# PlusBit_MCU.net
KiCad netlist of a schematic drawn in Altium Designer
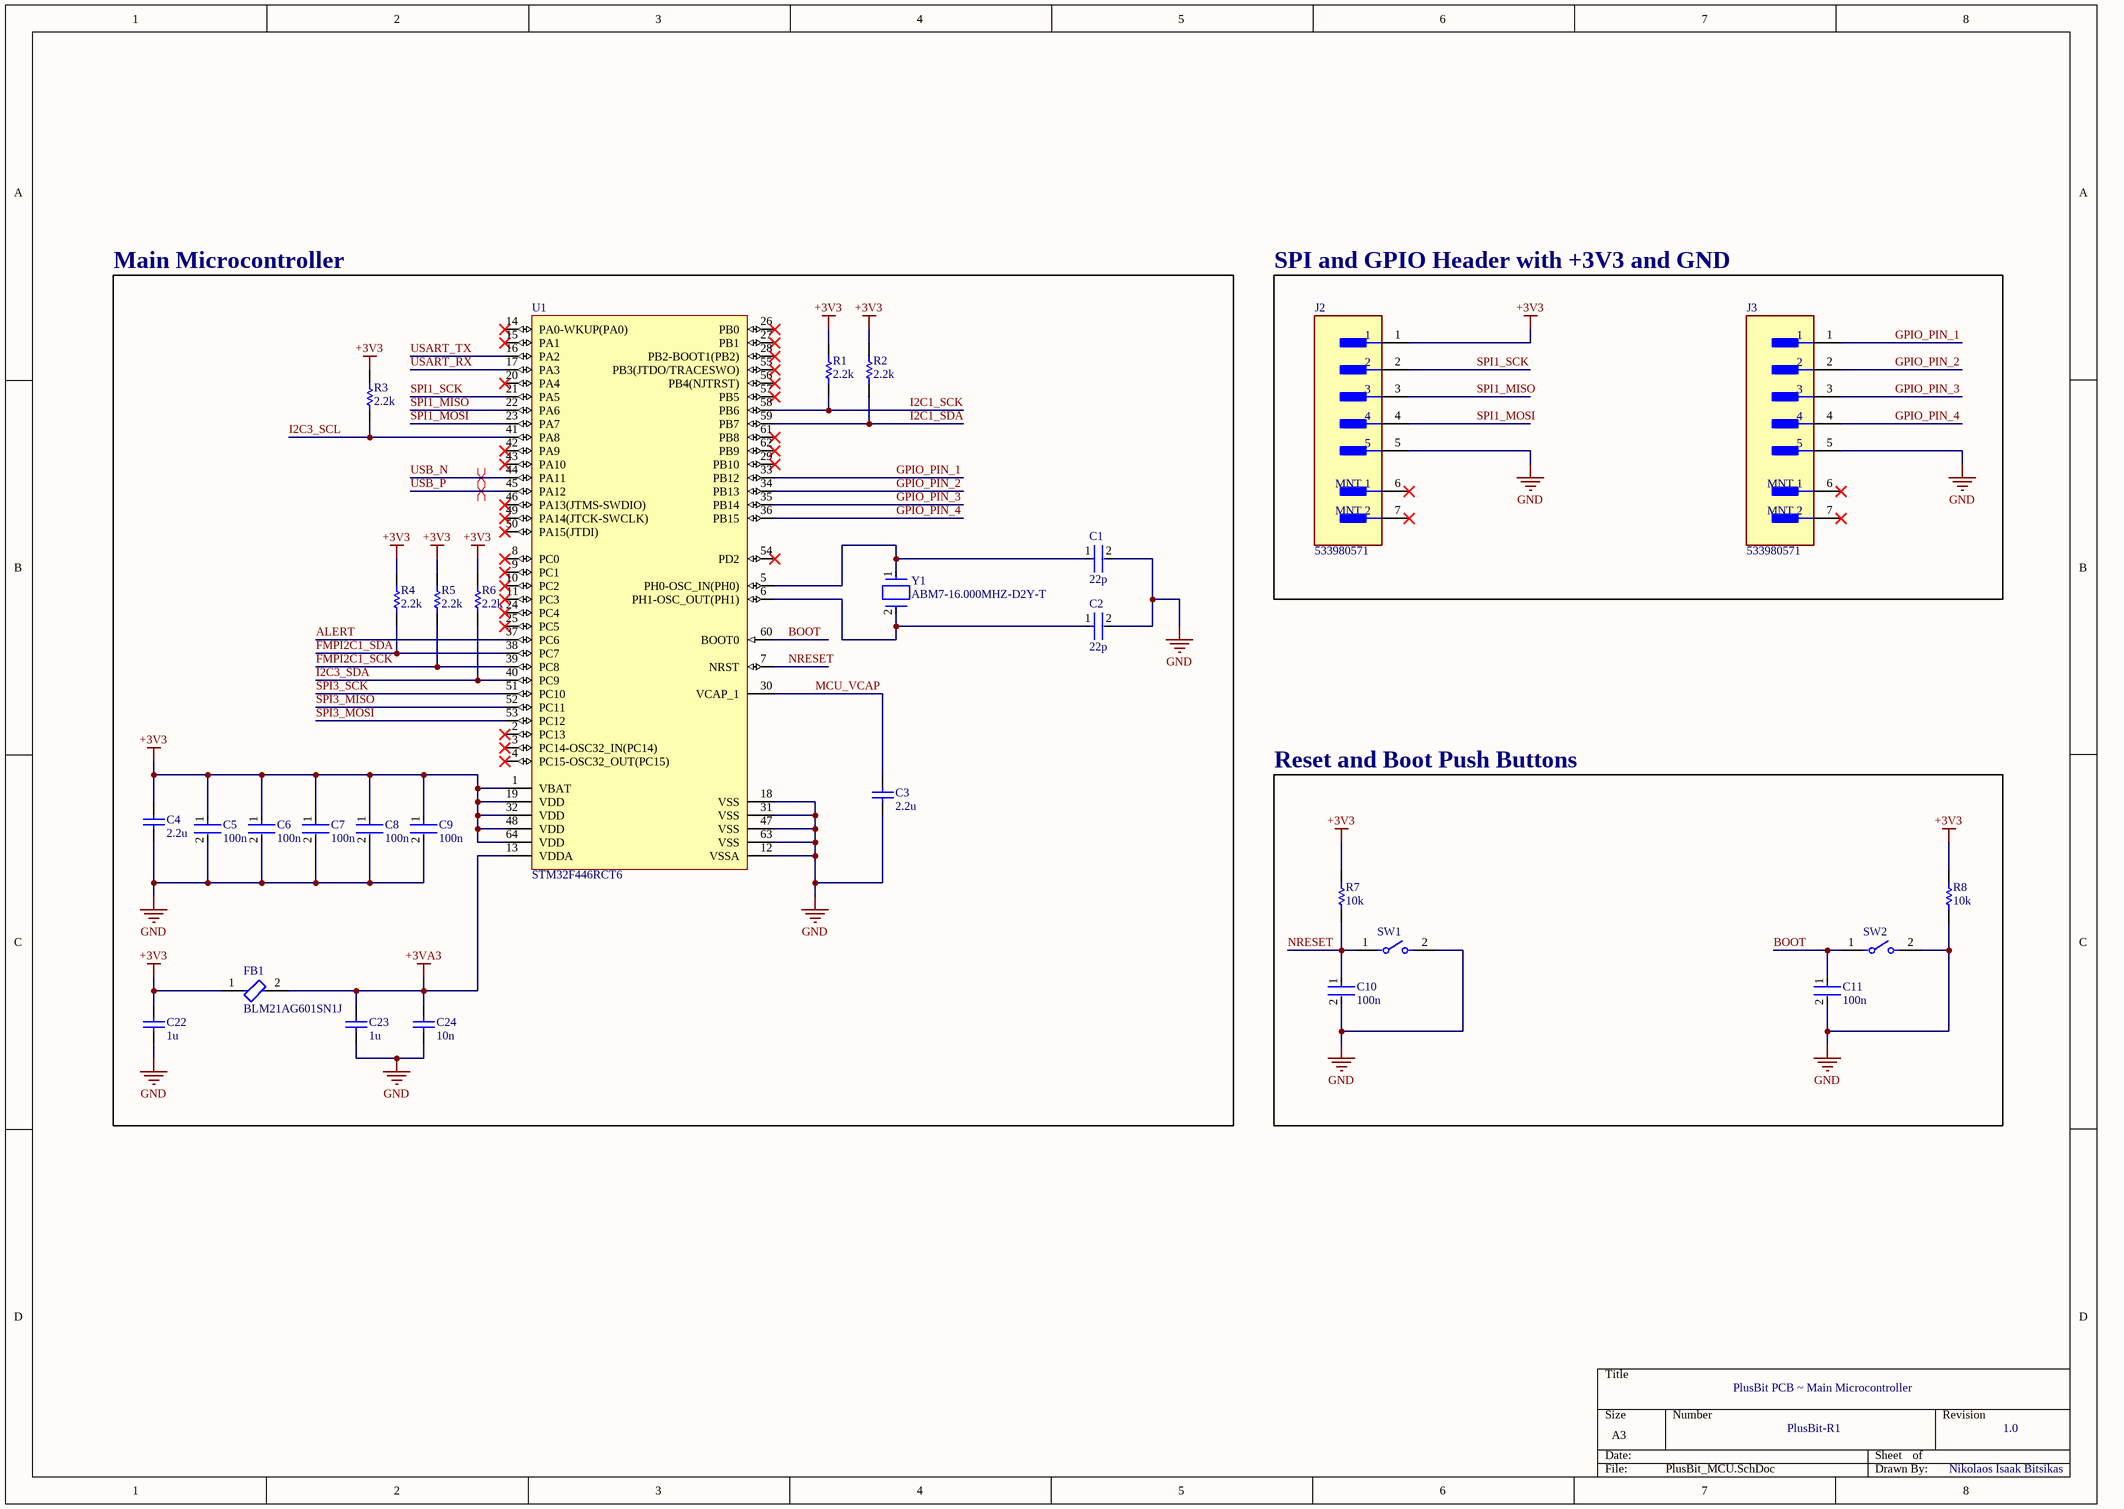
[diagram p0: PlusBit_MCU.SchDoc]

(export (version "E")
  (design (tool "Eeschema 10.0.6"))
  (components
    (comp (ref "C1")
      (value "22p")
      (footprint "FP-C1206C-EB-MFG")
      (description "1206 22pF Ceramic Multilayer Capacitor; 50VDC; 125degC; C0G Dielec; +/-5% SMD")
      (fields
        (field (name "OCTOPART") "https://octopart.com/c1206c220j5gactu-kemet-131912")
        (field (name "TOLERANCE") "0.05")
      )
      (libsource (lib "Altium Content Vault") (part "b4654b650e69147ec39a6b967a45e02"))
    )
    (comp (ref "C2")
      (value "22p")
      (footprint "FP-C1206C-EB-MFG")
      (description "1206 22pF Ceramic Multilayer Capacitor; 50VDC; 125degC; C0G Dielec; +/-5% SMD")
      (fields
        (field (name "OCTOPART") "https://octopart.com/c1206c220j5gactu-kemet-131912")
        (field (name "TOLERANCE") "0.05")
      )
      (libsource (lib "Altium Content Vault") (part "b4654b650e69147ec39a6b967a45e02"))
    )
    (comp (ref "C3")
      (value "2.2u")
      (footprint "CAPC2013X145X50ML20T25")
      (fields (field (name "PART NUMBER") "C0805C225K9PACTU") (field (name "MANUFACTURER") "Kemet"))
      (libsource (lib "Altium Content Vault") (part "CAP"))
    )
    (comp (ref "C4")
      (value "2.2u")
      (footprint "CAPC2013X145X50ML20T25")
      (fields (field (name "PART NUMBER") "C0805C225K9PACTU") (field (name "MANUFACTURER") "Kemet"))
      (libsource (lib "Altium Content Vault") (part "CAP"))
    )
    (comp (ref "C5")
      (value "100n")
      (footprint "FP-C0402-BB-MFG")
      (description "CAP CER 0.1UF 10V X5R 0402")
      (fields (field (name "MANUFACTURER") "Kemet") (field (name "TOLERANCE") "0.1"))
      (libsource (lib "Altium Content Vault") (part "b4654b650e69147ec39a6b967a45e02"))
    )
    (comp (ref "C6")
      (value "100n")
      (footprint "FP-C0402-BB-MFG")
      (description "CAP CER 0.1UF 10V X5R 0402")
      (fields (field (name "MANUFACTURER") "Kemet") (field (name "TOLERANCE") "0.1"))
      (libsource (lib "Altium Content Vault") (part "b4654b650e69147ec39a6b967a45e02"))
    )
    (comp (ref "C7")
      (value "100n")
      (footprint "FP-C0402-BB-MFG")
      (description "CAP CER 0.1UF 10V X5R 0402")
      (fields (field (name "MANUFACTURER") "Kemet") (field (name "TOLERANCE") "0.1"))
      (libsource (lib "Altium Content Vault") (part "b4654b650e69147ec39a6b967a45e02"))
    )
    (comp (ref "C8")
      (value "100n")
      (footprint "FP-C0402-BB-MFG")
      (description "CAP CER 0.1UF 10V X5R 0402")
      (fields (field (name "MANUFACTURER") "Kemet") (field (name "TOLERANCE") "0.1"))
      (libsource (lib "Altium Content Vault") (part "b4654b650e69147ec39a6b967a45e02"))
    )
    (comp (ref "C9")
      (value "100n")
      (footprint "FP-C0402-BB-MFG")
      (description "CAP CER 0.1UF 10V X5R 0402")
      (fields (field (name "MANUFACTURER") "Kemet") (field (name "TOLERANCE") "0.1"))
      (libsource (lib "Altium Content Vault") (part "b4654b650e69147ec39a6b967a45e02"))
    )
    (comp (ref "C10")
      (value "100n")
      (footprint "FP-C0402-BB-MFG")
      (description "CAP CER 0.1UF 16V X7R 0402")
      (fields
        (field (name "TOLERANCE") "0.1")
        (field (name "OCTOPART") "https://octopart.com/c0402c104k4ractu-kemet-94158")
      )
      (libsource (lib "Altium Content Vault") (part "b4654b650e69147ec39a6b967a45e02"))
    )
    (comp (ref "C11")
      (value "100n")
      (footprint "FP-C0402-BB-MFG")
      (description "CAP CER 0.1UF 10V X5R 0402")
      (fields (field (name "MANUFACTURER") "Kemet") (field (name "TOLERANCE") "0.1"))
      (libsource (lib "Altium Content Vault") (part "b4654b650e69147ec39a6b967a45e02"))
    )
    (comp (ref "C22")
      (value "1u")
      (footprint "CAPC2013X135X45LL10T25")
      (fields (field (name "MANUFACTURER") "Murata") (field (name "PART NUMBER") "GRM21BR71H105KA12L"))
      (libsource (lib "Altium Content Vault") (part "CAP"))
    )
    (comp (ref "C23")
      (value "1u")
      (footprint "CAPC2013X135X45LL10T25")
      (fields (field (name "MANUFACTURER") "Murata") (field (name "PART NUMBER") "GRM21BR71H105KA12L"))
      (libsource (lib "Altium Content Vault") (part "CAP"))
    )
    (comp (ref "C24")
      (value "10n")
      (footprint "CAPC2013X88X50LL20T25")
      (fields (field (name "MANUFACTURER") "Kemet") (field (name "PART NUMBER") "C0805C103K5RACTU"))
      (libsource (lib "Altium Content Vault") (part "CAP"))
    )
    (comp (ref "FB1")
      (value "BLM21AG601SN1J")
      (footprint "FP-BLM21-0_2-t0_85-e0_5-IPC_A")
      (description "Chip Ferrite Bead, 0805, 600Ω @ 100MHz, 0.2Ω, 25%, 700mA")
      (fields (field (name "TOLERANCE") "25%"))
      (libsource (lib "Altium Content Vault") (part "5f30dd21d616792df468990f7003faa"))
    )
    (comp (ref "J2")
      (value "533980571")
      (footprint "FP-533980571-MFG")
      (description "CONN HEADER SMD 5POS 1.25MM")
      (fields
        (field (name "MANUFACTURER") "Molex")
        (field (name "OCTOPART") "https://octopart.com/53398-0571-molex-655292")
      )
      (libsource (lib "Altium Content Vault") (part "6850237a4f4b29aa870910a3747ee34"))
    )
    (comp (ref "J3")
      (value "533980571")
      (footprint "FP-533980571-MFG")
      (description "CONN HEADER SMD 5POS 1.25MM")
      (fields
        (field (name "MANUFACTURER") "Molex")
        (field (name "OCTOPART") "https://octopart.com/53398-0571-molex-655292")
      )
      (libsource (lib "Altium Content Vault") (part "6850237a4f4b29aa870910a3747ee34"))
    )
    (comp (ref "R1")
      (value "2.2k")
      (footprint "RESC1608X55X25LL10T15")
      (fields (field (name "TOLERANCE") "1%") (field (name "MANUFACTURER") "Yageo"))
      (libsource (lib "Altium Content Vault") (part "RES-2"))
    )
    (comp (ref "R2")
      (value "2.2k")
      (footprint "RESC1608X55X25LL10T15")
      (fields (field (name "TOLERANCE") "1%") (field (name "MANUFACTURER") "Yageo"))
      (libsource (lib "Altium Content Vault") (part "RES-2"))
    )
    (comp (ref "R3")
      (value "2.2k")
      (footprint "RESC1608X55X25LL10T15")
      (fields (field (name "TOLERANCE") "1%") (field (name "MANUFACTURER") "Yageo"))
      (libsource (lib "Altium Content Vault") (part "RES-2"))
    )
    (comp (ref "R4")
      (value "2.2k")
      (footprint "RESC1608X55X25LL10T15")
      (fields (field (name "TOLERANCE") "1%") (field (name "MANUFACTURER") "Yageo"))
      (libsource (lib "Altium Content Vault") (part "RES-2"))
    )
    (comp (ref "R5")
      (value "2.2k")
      (footprint "RESC1608X55X25LL10T15")
      (fields (field (name "TOLERANCE") "1%") (field (name "MANUFACTURER") "Yageo"))
      (libsource (lib "Altium Content Vault") (part "RES-2"))
    )
    (comp (ref "R6")
      (value "2.2k")
      (footprint "RESC1608X55X25LL10T15")
      (fields (field (name "TOLERANCE") "1%") (field (name "MANUFACTURER") "Yageo"))
      (libsource (lib "Altium Content Vault") (part "RES-2"))
    )
    (comp (ref "R7")
      (value "10k")
      (footprint "RESC2013X60X35NL10T20")
      (description "Chip Resistor, 10 KOhm, +/- 1%, 0.125 W, -55 to 155 degC, 0805 (2012 Metric), RoHS, Tape and Reel")
      (fields (field (name "MANUFACTURER") "Yageo"))
      (libsource (lib "Altium Content Vault") (part "RES-2"))
    )
    (comp (ref "R8")
      (value "10k")
      (footprint "RESC1608X55X25ML10T15")
      (description "Resistor, 10 KOhm, +/- 5%, 100 mW, -55 to 155 degC, 0603 (1608 Metric), RoHS, Tape and Reel")
      (fields (field (name "MANUFACTURER") "Yageo") (field (name "TOLERANCE") "5%"))
      (libsource (lib "Altium Content Vault") (part "RES-2"))
    )
    (comp (ref "SW1")
      (value "FSM2JART")
      (footprint "FP-FSM2JART-MFG")
      (description "SWITCH TACTILE SPST-NO 0.05A 12V")
      (libsource (lib "Altium Content Vault") (part "bb27bde45df87f1f469753f287ef5ae"))
    )
    (comp (ref "SW2")
      (value "FSM2JART")
      (footprint "FP-FSM2JART-MFG")
      (description "SWITCH TACTILE SPST-NO 0.05A 12V")
      (libsource (lib "Altium Content Vault") (part "bb27bde45df87f1f469753f287ef5ae"))
    )
    (comp (ref "U1")
      (value "STM32F446RCT6")
      (footprint "STM-LQFP64_L")
      (libsource (lib "Altium Content Vault") (part "MC-ARM-STM32F446-LQFP64"))
    )
    (comp (ref "Y1")
      (value "ABM7-16.000MHZ-D2Y-T")
      (footprint "FP-ABM7-MFG")
      (description "Crystal 16MHz ±20ppm 18pF SMD-2 6mm x 3.5mm")
      (fields (field (name "TOLERANCE") "20ppm"))
      (libsource (lib "Altium Content Vault") (part "c23a69dc6c9e2f18f2079038eb95dd1"))
    )
  )
  (nets
    (net (code "1") (name "+3V3") (class "Default")
      (node (ref "C22") (pin "2") (pinfunction "2_2") (pintype "passive"))
      (node (ref "C4") (pin "2") (pinfunction "2_2") (pintype "passive"))
      (node (ref "C5") (pin "1") (pinfunction "1_1") (pintype "passive"))
      (node (ref "C6") (pin "1") (pinfunction "1_1") (pintype "passive"))
      (node (ref "C7") (pin "1") (pinfunction "1_1") (pintype "passive"))
      (node (ref "C8") (pin "1") (pinfunction "1_1") (pintype "passive"))
      (node (ref "C9") (pin "1") (pinfunction "1_1") (pintype "passive"))
      (node (ref "FB1") (pin "1") (pinfunction "1_1") (pintype "passive"))
      (node (ref "J2") (pin "1") (pinfunction "1_1") (pintype "passive"))
      (node (ref "R1") (pin "2") (pinfunction "2_2") (pintype "passive"))
      (node (ref "R2") (pin "2") (pinfunction "2_2") (pintype "passive"))
      (node (ref "R3") (pin "2") (pinfunction "2_2") (pintype "passive"))
      (node (ref "R4") (pin "2") (pinfunction "2_2") (pintype "passive"))
      (node (ref "R5") (pin "2") (pinfunction "2_2") (pintype "passive"))
      (node (ref "R6") (pin "2") (pinfunction "2_2") (pintype "passive"))
      (node (ref "R7") (pin "2") (pinfunction "2_2") (pintype "passive"))
      (node (ref "R8") (pin "2") (pinfunction "2_2") (pintype "passive"))
      (node (ref "U1") (pin "1") (pinfunction "VBAT_1") (pintype "power_in"))
      (node (ref "U1") (pin "19") (pinfunction "VDD_19") (pintype "power_in"))
      (node (ref "U1") (pin "32") (pinfunction "VDD_32") (pintype "power_in"))
      (node (ref "U1") (pin "48") (pinfunction "VDD_48") (pintype "power_in"))
      (node (ref "U1") (pin "64") (pinfunction "VDD_64") (pintype "power_in"))
    )
    (net (code "2") (name "+3VA3") (class "Default")
      (node (ref "C23") (pin "2") (pinfunction "2_2") (pintype "passive"))
      (node (ref "C24") (pin "2") (pinfunction "2_2") (pintype "passive"))
      (node (ref "FB1") (pin "2") (pinfunction "2_2") (pintype "passive"))
      (node (ref "U1") (pin "13") (pinfunction "VDDA_13") (pintype "power_in"))
    )
    (net (code "3") (name "/ALERT") (class "Default")
      (node (ref "U1") (pin "37") (pinfunction "PC6_37") (pintype "bidirectional"))
    )
    (net (code "4") (name "/BOOT") (class "Default")
      (node (ref "C11") (pin "1") (pinfunction "1_1") (pintype "passive"))
      (node (ref "SW2") (pin "1") (pinfunction "1_1") (pintype "passive"))
      (node (ref "U1") (pin "60") (pinfunction "BOOT0_60") (pintype "input"))
    )
    (net (code "5") (name "/FMPI2C1_SCK") (class "Default")
      (node (ref "R5") (pin "1") (pinfunction "1_1") (pintype "passive"))
      (node (ref "U1") (pin "39") (pinfunction "PC8_39") (pintype "bidirectional"))
    )
    (net (code "6") (name "/FMPI2C1_SDA") (class "Default")
      (node (ref "R4") (pin "1") (pinfunction "1_1") (pintype "passive"))
      (node (ref "U1") (pin "38") (pinfunction "PC7_38") (pintype "bidirectional"))
    )
    (net (code "7") (name "/GPIO_PIN_1") (class "Default")
      (node (ref "J3") (pin "1") (pinfunction "1_1") (pintype "passive"))
      (node (ref "U1") (pin "33") (pinfunction "PB12_33") (pintype "bidirectional"))
    )
    (net (code "8") (name "/GPIO_PIN_2") (class "Default")
      (node (ref "J3") (pin "2") (pinfunction "2_2") (pintype "passive"))
      (node (ref "U1") (pin "34") (pinfunction "PB13_34") (pintype "bidirectional"))
    )
    (net (code "9") (name "/GPIO_PIN_3") (class "Default")
      (node (ref "J3") (pin "3") (pinfunction "3_3") (pintype "passive"))
      (node (ref "U1") (pin "35") (pinfunction "PB14_35") (pintype "bidirectional"))
    )
    (net (code "10") (name "/GPIO_PIN_4") (class "Default")
      (node (ref "J3") (pin "4") (pinfunction "4_4") (pintype "passive"))
      (node (ref "U1") (pin "36") (pinfunction "PB15_36") (pintype "bidirectional"))
    )
    (net (code "11") (name "/I2C1_SCK") (class "Default")
      (node (ref "R1") (pin "1") (pinfunction "1_1") (pintype "passive"))
      (node (ref "U1") (pin "58") (pinfunction "PB6_58") (pintype "bidirectional"))
    )
    (net (code "12") (name "/I2C1_SDA") (class "Default")
      (node (ref "R2") (pin "1") (pinfunction "1_1") (pintype "passive"))
      (node (ref "U1") (pin "59") (pinfunction "PB7_59") (pintype "bidirectional"))
    )
    (net (code "13") (name "/I2C3_SCL") (class "Default")
      (node (ref "R3") (pin "1") (pinfunction "1_1") (pintype "passive"))
      (node (ref "U1") (pin "41") (pinfunction "PA8_41") (pintype "bidirectional"))
    )
    (net (code "14") (name "/I2C3_SDA") (class "Default")
      (node (ref "R6") (pin "1") (pinfunction "1_1") (pintype "passive"))
      (node (ref "U1") (pin "40") (pinfunction "PC9_40") (pintype "bidirectional"))
    )
    (net (code "15") (name "/MCU_VCAP") (class "Default")
      (node (ref "C3") (pin "2") (pinfunction "2_2") (pintype "passive"))
      (node (ref "U1") (pin "30") (pinfunction "VCAP_1_30") (pintype "passive"))
    )
    (net (code "16") (name "/NRESET") (class "Default")
      (node (ref "C10") (pin "1") (pinfunction "1_1") (pintype "passive"))
      (node (ref "R7") (pin "1") (pinfunction "1_1") (pintype "passive"))
      (node (ref "SW1") (pin "1") (pinfunction "1_1") (pintype "passive"))
      (node (ref "U1") (pin "7") (pinfunction "NRST_7") (pintype "bidirectional"))
    )
    (net (code "17") (name "/SPI1_MISO") (class "Default")
      (node (ref "J2") (pin "3") (pinfunction "3_3") (pintype "passive"))
      (node (ref "U1") (pin "22") (pinfunction "PA6_22") (pintype "bidirectional"))
    )
    (net (code "18") (name "/SPI1_MOSI") (class "Default")
      (node (ref "J2") (pin "4") (pinfunction "4_4") (pintype "passive"))
      (node (ref "U1") (pin "23") (pinfunction "PA7_23") (pintype "bidirectional"))
    )
    (net (code "19") (name "/SPI1_SCK") (class "Default")
      (node (ref "J2") (pin "2") (pinfunction "2_2") (pintype "passive"))
      (node (ref "U1") (pin "21") (pinfunction "PA5_21") (pintype "bidirectional"))
    )
    (net (code "20") (name "/SPI3_MISO") (class "Default")
      (node (ref "U1") (pin "52") (pinfunction "PC11_52") (pintype "bidirectional"))
    )
    (net (code "21") (name "/SPI3_MOSI") (class "Default")
      (node (ref "U1") (pin "53") (pinfunction "PC12_53") (pintype "bidirectional"))
    )
    (net (code "22") (name "/SPI3_SCK") (class "Default")
      (node (ref "U1") (pin "51") (pinfunction "PC10_51") (pintype "bidirectional"))
    )
    (net (code "23") (name "/USART_RX") (class "Default")
      (node (ref "U1") (pin "17") (pinfunction "PA3_17") (pintype "bidirectional"))
    )
    (net (code "24") (name "/USART_TX") (class "Default")
      (node (ref "U1") (pin "16") (pinfunction "PA2_16") (pintype "bidirectional"))
    )
    (net (code "25") (name "/USB_N") (class "Default")
      (node (ref "U1") (pin "44") (pinfunction "PA11_44") (pintype "bidirectional"))
    )
    (net (code "26") (name "/USB_P") (class "Default")
      (node (ref "U1") (pin "45") (pinfunction "PA12_45") (pintype "bidirectional"))
    )
    (net (code "27") (name "GND") (class "Default")
      (node (ref "C1") (pin "2") (pinfunction "2_2") (pintype "passive"))
      (node (ref "C10") (pin "2") (pinfunction "2_2") (pintype "passive"))
      (node (ref "C11") (pin "2") (pinfunction "2_2") (pintype "passive"))
      (node (ref "C2") (pin "2") (pinfunction "2_2") (pintype "passive"))
      (node (ref "C22") (pin "1") (pinfunction "1_1") (pintype "passive"))
      (node (ref "C23") (pin "1") (pinfunction "1_1") (pintype "passive"))
      (node (ref "C24") (pin "1") (pinfunction "1_1") (pintype "passive"))
      (node (ref "C3") (pin "1") (pinfunction "1_1") (pintype "passive"))
      (node (ref "C4") (pin "1") (pinfunction "1_1") (pintype "passive"))
      (node (ref "C5") (pin "2") (pinfunction "2_2") (pintype "passive"))
      (node (ref "C6") (pin "2") (pinfunction "2_2") (pintype "passive"))
      (node (ref "C7") (pin "2") (pinfunction "2_2") (pintype "passive"))
      (node (ref "C8") (pin "2") (pinfunction "2_2") (pintype "passive"))
      (node (ref "C9") (pin "2") (pinfunction "2_2") (pintype "passive"))
      (node (ref "J2") (pin "5") (pinfunction "5_5") (pintype "passive"))
      (node (ref "J3") (pin "5") (pinfunction "5_5") (pintype "passive"))
      (node (ref "R8") (pin "1") (pinfunction "1_1") (pintype "passive"))
      (node (ref "SW1") (pin "2") (pinfunction "2_2") (pintype "passive"))
      (node (ref "SW2") (pin "2") (pinfunction "2_2") (pintype "passive"))
      (node (ref "U1") (pin "12") (pinfunction "VSSA_12") (pintype "power_in"))
      (node (ref "U1") (pin "18") (pinfunction "VSS_18") (pintype "power_in"))
      (node (ref "U1") (pin "31") (pinfunction "VSS_31") (pintype "power_in"))
      (node (ref "U1") (pin "47") (pinfunction "VSS_47") (pintype "power_in"))
      (node (ref "U1") (pin "63") (pinfunction "VSS_63") (pintype "power_in"))
    )
    (net (code "28") (name "Net-(U1-PH0-OSC_IN(PH0))") (class "Default")
      (node (ref "C1") (pin "1") (pinfunction "1_1") (pintype "passive"))
      (node (ref "U1") (pin "5") (pinfunction "PH0-OSC_IN(PH0)_5") (pintype "bidirectional"))
      (node (ref "Y1") (pin "1") (pinfunction "1_1") (pintype "passive"))
    )
    (net (code "29") (name "Net-(U1-PH1-OSC_OUT(PH1))") (class "Default")
      (node (ref "C2") (pin "1") (pinfunction "1_1") (pintype "passive"))
      (node (ref "U1") (pin "6") (pinfunction "PH1-OSC_OUT(PH1)_6") (pintype "bidirectional"))
      (node (ref "Y1") (pin "2") (pinfunction "2_2") (pintype "passive"))
    )
    (net (code "30") (name "unconnected-(J2-MNT_1-Pad6)") (class "Default")
      (node (ref "J2") (pin "6") (pinfunction "MNT_1_6") (pintype "passive+no_connect"))
    )
    (net (code "31") (name "unconnected-(J2-MNT_2-Pad7)") (class "Default")
      (node (ref "J2") (pin "7") (pinfunction "MNT_2_7") (pintype "passive+no_connect"))
    )
    (net (code "32") (name "unconnected-(J3-MNT_1-Pad6)") (class "Default")
      (node (ref "J3") (pin "6") (pinfunction "MNT_1_6") (pintype "passive+no_connect"))
    )
    (net (code "33") (name "unconnected-(J3-MNT_2-Pad7)") (class "Default")
      (node (ref "J3") (pin "7") (pinfunction "MNT_2_7") (pintype "passive+no_connect"))
    )
    (net (code "34") (name "unconnected-(U1-PA0-WKUP(PA0)-Pad14)") (class "Default")
      (node (ref "U1") (pin "14") (pinfunction "PA0-WKUP(PA0)_14") (pintype "bidirectional+no_connect"))
    )
    (net (code "35") (name "unconnected-(U1-PA1-Pad15)") (class "Default")
      (node (ref "U1") (pin "15") (pinfunction "PA1_15") (pintype "bidirectional+no_connect"))
    )
    (net (code "36") (name "unconnected-(U1-PA4-Pad20)") (class "Default")
      (node (ref "U1") (pin "20") (pinfunction "PA4_20") (pintype "bidirectional+no_connect"))
    )
    (net (code "37") (name "unconnected-(U1-PA9-Pad42)") (class "Default")
      (node (ref "U1") (pin "42") (pinfunction "PA9_42") (pintype "bidirectional+no_connect"))
    )
    (net (code "38") (name "unconnected-(U1-PA10-Pad43)") (class "Default")
      (node (ref "U1") (pin "43") (pinfunction "PA10_43") (pintype "bidirectional+no_connect"))
    )
    (net (code "39") (name "unconnected-(U1-PA13(JTMS-SWDIO)-Pad46)") (class "Default")
      (node (ref "U1") (pin "46") (pinfunction "PA13(JTMS-SWDIO)_46") (pintype "bidirectional+no_connect"))
    )
    (net (code "40") (name "unconnected-(U1-PA14(JTCK-SWCLK)-Pad49)") (class "Default")
      (node (ref "U1") (pin "49") (pinfunction "PA14(JTCK-SWCLK)_49") (pintype "bidirectional+no_connect"))
    )
    (net (code "41") (name "unconnected-(U1-PA15(JTDI)-Pad50)") (class "Default")
      (node (ref "U1") (pin "50") (pinfunction "PA15(JTDI)_50") (pintype "bidirectional+no_connect"))
    )
    (net (code "42") (name "unconnected-(U1-PB0-Pad26)") (class "Default")
      (node (ref "U1") (pin "26") (pinfunction "PB0_26") (pintype "bidirectional+no_connect"))
    )
    (net (code "43") (name "unconnected-(U1-PB1-Pad27)") (class "Default")
      (node (ref "U1") (pin "27") (pinfunction "PB1_27") (pintype "bidirectional+no_connect"))
    )
    (net (code "44") (name "unconnected-(U1-PB2-BOOT1(PB2)-Pad28)") (class "Default")
      (node (ref "U1") (pin "28") (pinfunction "PB2-BOOT1(PB2)_28") (pintype "bidirectional+no_connect"))
    )
    (net (code "45") (name "unconnected-(U1-PB3(JTDO{slash}TRACESWO)-Pad55)") (class "Default")
      (node (ref "U1") (pin "55") (pinfunction "PB3(JTDO/TRACESWO)_55") (pintype "bidirectional+no_connect"))
    )
    (net (code "46") (name "unconnected-(U1-PB4(NJTRST)-Pad56)") (class "Default")
      (node (ref "U1") (pin "56") (pinfunction "PB4(NJTRST)_56") (pintype "bidirectional+no_connect"))
    )
    (net (code "47") (name "unconnected-(U1-PB5-Pad57)") (class "Default")
      (node (ref "U1") (pin "57") (pinfunction "PB5_57") (pintype "bidirectional+no_connect"))
    )
    (net (code "48") (name "unconnected-(U1-PB8-Pad61)") (class "Default")
      (node (ref "U1") (pin "61") (pinfunction "PB8_61") (pintype "bidirectional+no_connect"))
    )
    (net (code "49") (name "unconnected-(U1-PB9-Pad62)") (class "Default")
      (node (ref "U1") (pin "62") (pinfunction "PB9_62") (pintype "bidirectional+no_connect"))
    )
    (net (code "50") (name "unconnected-(U1-PB10-Pad29)") (class "Default")
      (node (ref "U1") (pin "29") (pinfunction "PB10_29") (pintype "bidirectional+no_connect"))
    )
    (net (code "51") (name "unconnected-(U1-PC0-Pad8)") (class "Default")
      (node (ref "U1") (pin "8") (pinfunction "PC0_8") (pintype "bidirectional+no_connect"))
    )
    (net (code "52") (name "unconnected-(U1-PC1-Pad9)") (class "Default")
      (node (ref "U1") (pin "9") (pinfunction "PC1_9") (pintype "bidirectional+no_connect"))
    )
    (net (code "53") (name "unconnected-(U1-PC2-Pad10)") (class "Default")
      (node (ref "U1") (pin "10") (pinfunction "PC2_10") (pintype "bidirectional+no_connect"))
    )
    (net (code "54") (name "unconnected-(U1-PC3-Pad11)") (class "Default")
      (node (ref "U1") (pin "11") (pinfunction "PC3_11") (pintype "bidirectional+no_connect"))
    )
    (net (code "55") (name "unconnected-(U1-PC4-Pad24)") (class "Default")
      (node (ref "U1") (pin "24") (pinfunction "PC4_24") (pintype "bidirectional+no_connect"))
    )
    (net (code "56") (name "unconnected-(U1-PC5-Pad25)") (class "Default")
      (node (ref "U1") (pin "25") (pinfunction "PC5_25") (pintype "bidirectional+no_connect"))
    )
    (net (code "57") (name "unconnected-(U1-PC13-Pad2)") (class "Default")
      (node (ref "U1") (pin "2") (pinfunction "PC13_2") (pintype "bidirectional+no_connect"))
    )
    (net (code "58") (name "unconnected-(U1-PC14-OSC32_IN(PC14)-Pad3)") (class "Default")
      (node (ref "U1") (pin "3") (pinfunction "PC14-OSC32_IN(PC14)_3") (pintype "bidirectional+no_connect"))
    )
    (net (code "59") (name "unconnected-(U1-PC15-OSC32_OUT(PC15)-Pad4)") (class "Default")
      (node (ref "U1") (pin "4") (pinfunction "PC15-OSC32_OUT(PC15)_4") (pintype "bidirectional+no_connect"))
    )
    (net (code "60") (name "unconnected-(U1-PD2-Pad54)") (class "Default")
      (node (ref "U1") (pin "54") (pinfunction "PD2_54") (pintype "bidirectional+no_connect"))
    )
  )
)
